# RGBM-06.net
KiCad netlist of a schematic drawn in Altium Designer
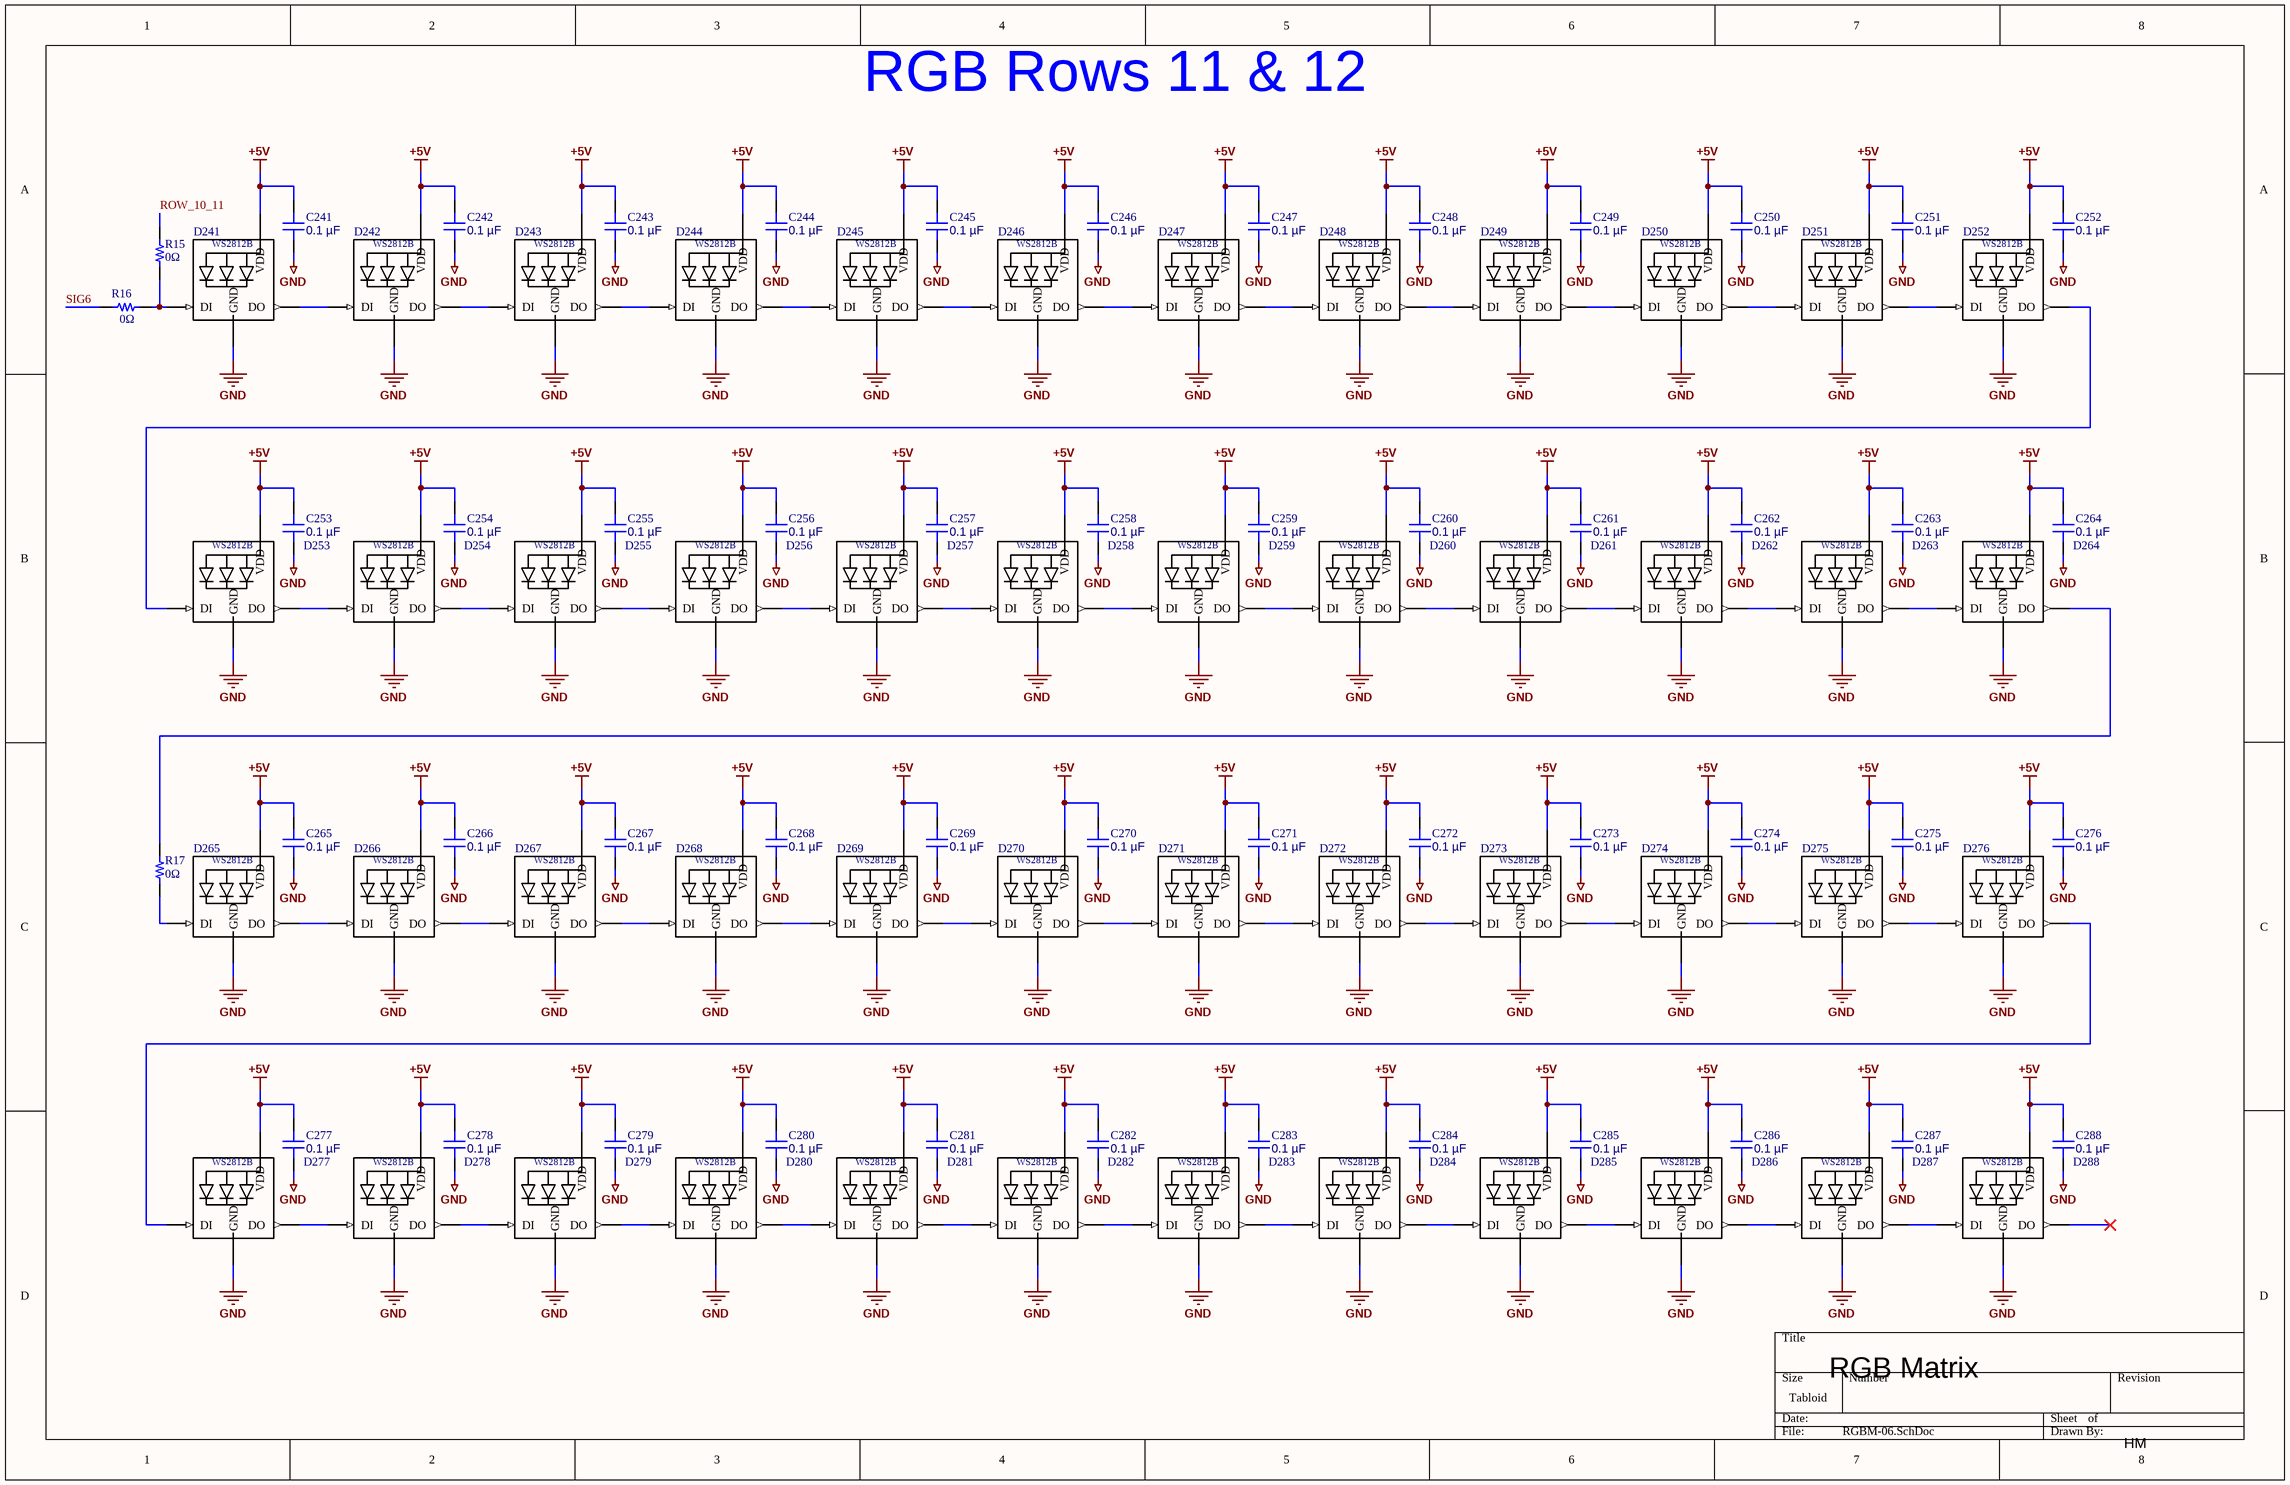
[diagram p0: RGBM-06.SchDoc]

(export (version "E")
  (design (tool "Eeschema 10.0.6"))
  (components
    (comp (ref "C241")
      (value "0.1 µF")
      (footprint "CAP 0603_1608")
      (description "CAP CER 0.1UF 50V X7R 0603")
      (fields
        (field (name "PART NUMBER") "C0603C104K5RAC7411")
        (field (name "CAPACITANCE") "0.1 µF")
        (field (name "MANUFACTURER") "KEMET")
      )
      (libsource (lib "Celestial Altium Library - altium_library") (part "Capacitor"))
    )
    (comp (ref "C242")
      (value "0.1 µF")
      (footprint "CAP 0603_1608")
      (description "CAP CER 0.1UF 50V X7R 0603")
      (fields
        (field (name "PART NUMBER") "C0603C104K5RAC7411")
        (field (name "CAPACITANCE") "0.1 µF")
        (field (name "MANUFACTURER") "KEMET")
      )
      (libsource (lib "Celestial Altium Library - altium_library") (part "Capacitor"))
    )
    (comp (ref "C243")
      (value "0.1 µF")
      (footprint "CAP 0603_1608")
      (description "CAP CER 0.1UF 50V X7R 0603")
      (fields
        (field (name "PART NUMBER") "C0603C104K5RAC7411")
        (field (name "CAPACITANCE") "0.1 µF")
        (field (name "MANUFACTURER") "KEMET")
      )
      (libsource (lib "Celestial Altium Library - altium_library") (part "Capacitor"))
    )
    (comp (ref "C244")
      (value "0.1 µF")
      (footprint "CAP 0603_1608")
      (description "CAP CER 0.1UF 50V X7R 0603")
      (fields
        (field (name "PART NUMBER") "C0603C104K5RAC7411")
        (field (name "CAPACITANCE") "0.1 µF")
        (field (name "MANUFACTURER") "KEMET")
      )
      (libsource (lib "Celestial Altium Library - altium_library") (part "Capacitor"))
    )
    (comp (ref "C245")
      (value "0.1 µF")
      (footprint "CAP 0603_1608")
      (description "CAP CER 0.1UF 50V X7R 0603")
      (fields
        (field (name "PART NUMBER") "C0603C104K5RAC7411")
        (field (name "CAPACITANCE") "0.1 µF")
        (field (name "MANUFACTURER") "KEMET")
      )
      (libsource (lib "Celestial Altium Library - altium_library") (part "Capacitor"))
    )
    (comp (ref "C246")
      (value "0.1 µF")
      (footprint "CAP 0603_1608")
      (description "CAP CER 0.1UF 50V X7R 0603")
      (fields
        (field (name "PART NUMBER") "C0603C104K5RAC7411")
        (field (name "CAPACITANCE") "0.1 µF")
        (field (name "MANUFACTURER") "KEMET")
      )
      (libsource (lib "Celestial Altium Library - altium_library") (part "Capacitor"))
    )
    (comp (ref "C247")
      (value "0.1 µF")
      (footprint "CAP 0603_1608")
      (description "CAP CER 0.1UF 50V X7R 0603")
      (fields
        (field (name "PART NUMBER") "C0603C104K5RAC7411")
        (field (name "CAPACITANCE") "0.1 µF")
        (field (name "MANUFACTURER") "KEMET")
      )
      (libsource (lib "Celestial Altium Library - altium_library") (part "Capacitor"))
    )
    (comp (ref "C248")
      (value "0.1 µF")
      (footprint "CAP 0603_1608")
      (description "CAP CER 0.1UF 50V X7R 0603")
      (fields
        (field (name "PART NUMBER") "C0603C104K5RAC7411")
        (field (name "CAPACITANCE") "0.1 µF")
        (field (name "MANUFACTURER") "KEMET")
      )
      (libsource (lib "Celestial Altium Library - altium_library") (part "Capacitor"))
    )
    (comp (ref "C249")
      (value "0.1 µF")
      (footprint "CAP 0603_1608")
      (description "CAP CER 0.1UF 50V X7R 0603")
      (fields
        (field (name "PART NUMBER") "C0603C104K5RAC7411")
        (field (name "CAPACITANCE") "0.1 µF")
        (field (name "MANUFACTURER") "KEMET")
      )
      (libsource (lib "Celestial Altium Library - altium_library") (part "Capacitor"))
    )
    (comp (ref "C250")
      (value "0.1 µF")
      (footprint "CAP 0603_1608")
      (description "CAP CER 0.1UF 50V X7R 0603")
      (fields
        (field (name "PART NUMBER") "C0603C104K5RAC7411")
        (field (name "CAPACITANCE") "0.1 µF")
        (field (name "MANUFACTURER") "KEMET")
      )
      (libsource (lib "Celestial Altium Library - altium_library") (part "Capacitor"))
    )
    (comp (ref "C251")
      (value "0.1 µF")
      (footprint "CAP 0603_1608")
      (description "CAP CER 0.1UF 50V X7R 0603")
      (fields
        (field (name "PART NUMBER") "C0603C104K5RAC7411")
        (field (name "CAPACITANCE") "0.1 µF")
        (field (name "MANUFACTURER") "KEMET")
      )
      (libsource (lib "Celestial Altium Library - altium_library") (part "Capacitor"))
    )
    (comp (ref "C252")
      (value "0.1 µF")
      (footprint "CAP 0603_1608")
      (description "CAP CER 0.1UF 50V X7R 0603")
      (fields
        (field (name "PART NUMBER") "C0603C104K5RAC7411")
        (field (name "CAPACITANCE") "0.1 µF")
        (field (name "MANUFACTURER") "KEMET")
      )
      (libsource (lib "Celestial Altium Library - altium_library") (part "Capacitor"))
    )
    (comp (ref "C253")
      (value "0.1 µF")
      (footprint "CAP 0603_1608")
      (description "CAP CER 0.1UF 50V X7R 0603")
      (fields
        (field (name "PART NUMBER") "C0603C104K5RAC7411")
        (field (name "CAPACITANCE") "0.1 µF")
        (field (name "MANUFACTURER") "KEMET")
      )
      (libsource (lib "Celestial Altium Library - altium_library") (part "Capacitor"))
    )
    (comp (ref "C254")
      (value "0.1 µF")
      (footprint "CAP 0603_1608")
      (description "CAP CER 0.1UF 50V X7R 0603")
      (fields
        (field (name "PART NUMBER") "C0603C104K5RAC7411")
        (field (name "CAPACITANCE") "0.1 µF")
        (field (name "MANUFACTURER") "KEMET")
      )
      (libsource (lib "Celestial Altium Library - altium_library") (part "Capacitor"))
    )
    (comp (ref "C255")
      (value "0.1 µF")
      (footprint "CAP 0603_1608")
      (description "CAP CER 0.1UF 50V X7R 0603")
      (fields
        (field (name "PART NUMBER") "C0603C104K5RAC7411")
        (field (name "CAPACITANCE") "0.1 µF")
        (field (name "MANUFACTURER") "KEMET")
      )
      (libsource (lib "Celestial Altium Library - altium_library") (part "Capacitor"))
    )
    (comp (ref "C256")
      (value "0.1 µF")
      (footprint "CAP 0603_1608")
      (description "CAP CER 0.1UF 50V X7R 0603")
      (fields
        (field (name "PART NUMBER") "C0603C104K5RAC7411")
        (field (name "CAPACITANCE") "0.1 µF")
        (field (name "MANUFACTURER") "KEMET")
      )
      (libsource (lib "Celestial Altium Library - altium_library") (part "Capacitor"))
    )
    (comp (ref "C257")
      (value "0.1 µF")
      (footprint "CAP 0603_1608")
      (description "CAP CER 0.1UF 50V X7R 0603")
      (fields
        (field (name "PART NUMBER") "C0603C104K5RAC7411")
        (field (name "CAPACITANCE") "0.1 µF")
        (field (name "MANUFACTURER") "KEMET")
      )
      (libsource (lib "Celestial Altium Library - altium_library") (part "Capacitor"))
    )
    (comp (ref "C258")
      (value "0.1 µF")
      (footprint "CAP 0603_1608")
      (description "CAP CER 0.1UF 50V X7R 0603")
      (fields
        (field (name "PART NUMBER") "C0603C104K5RAC7411")
        (field (name "CAPACITANCE") "0.1 µF")
        (field (name "MANUFACTURER") "KEMET")
      )
      (libsource (lib "Celestial Altium Library - altium_library") (part "Capacitor"))
    )
    (comp (ref "C259")
      (value "0.1 µF")
      (footprint "CAP 0603_1608")
      (description "CAP CER 0.1UF 50V X7R 0603")
      (fields
        (field (name "PART NUMBER") "C0603C104K5RAC7411")
        (field (name "CAPACITANCE") "0.1 µF")
        (field (name "MANUFACTURER") "KEMET")
      )
      (libsource (lib "Celestial Altium Library - altium_library") (part "Capacitor"))
    )
    (comp (ref "C260")
      (value "0.1 µF")
      (footprint "CAP 0603_1608")
      (description "CAP CER 0.1UF 50V X7R 0603")
      (fields
        (field (name "PART NUMBER") "C0603C104K5RAC7411")
        (field (name "CAPACITANCE") "0.1 µF")
        (field (name "MANUFACTURER") "KEMET")
      )
      (libsource (lib "Celestial Altium Library - altium_library") (part "Capacitor"))
    )
    (comp (ref "C261")
      (value "0.1 µF")
      (footprint "CAP 0603_1608")
      (description "CAP CER 0.1UF 50V X7R 0603")
      (fields
        (field (name "PART NUMBER") "C0603C104K5RAC7411")
        (field (name "CAPACITANCE") "0.1 µF")
        (field (name "MANUFACTURER") "KEMET")
      )
      (libsource (lib "Celestial Altium Library - altium_library") (part "Capacitor"))
    )
    (comp (ref "C262")
      (value "0.1 µF")
      (footprint "CAP 0603_1608")
      (description "CAP CER 0.1UF 50V X7R 0603")
      (fields
        (field (name "PART NUMBER") "C0603C104K5RAC7411")
        (field (name "CAPACITANCE") "0.1 µF")
        (field (name "MANUFACTURER") "KEMET")
      )
      (libsource (lib "Celestial Altium Library - altium_library") (part "Capacitor"))
    )
    (comp (ref "C263")
      (value "0.1 µF")
      (footprint "CAP 0603_1608")
      (description "CAP CER 0.1UF 50V X7R 0603")
      (fields
        (field (name "PART NUMBER") "C0603C104K5RAC7411")
        (field (name "CAPACITANCE") "0.1 µF")
        (field (name "MANUFACTURER") "KEMET")
      )
      (libsource (lib "Celestial Altium Library - altium_library") (part "Capacitor"))
    )
    (comp (ref "C264")
      (value "0.1 µF")
      (footprint "CAP 0603_1608")
      (description "CAP CER 0.1UF 50V X7R 0603")
      (fields
        (field (name "PART NUMBER") "C0603C104K5RAC7411")
        (field (name "CAPACITANCE") "0.1 µF")
        (field (name "MANUFACTURER") "KEMET")
      )
      (libsource (lib "Celestial Altium Library - altium_library") (part "Capacitor"))
    )
    (comp (ref "C265")
      (value "0.1 µF")
      (footprint "CAP 0603_1608")
      (description "CAP CER 0.1UF 50V X7R 0603")
      (fields
        (field (name "PART NUMBER") "C0603C104K5RAC7411")
        (field (name "CAPACITANCE") "0.1 µF")
        (field (name "MANUFACTURER") "KEMET")
      )
      (libsource (lib "Celestial Altium Library - altium_library") (part "Capacitor"))
    )
    (comp (ref "C266")
      (value "0.1 µF")
      (footprint "CAP 0603_1608")
      (description "CAP CER 0.1UF 50V X7R 0603")
      (fields
        (field (name "PART NUMBER") "C0603C104K5RAC7411")
        (field (name "CAPACITANCE") "0.1 µF")
        (field (name "MANUFACTURER") "KEMET")
      )
      (libsource (lib "Celestial Altium Library - altium_library") (part "Capacitor"))
    )
    (comp (ref "C267")
      (value "0.1 µF")
      (footprint "CAP 0603_1608")
      (description "CAP CER 0.1UF 50V X7R 0603")
      (fields
        (field (name "PART NUMBER") "C0603C104K5RAC7411")
        (field (name "CAPACITANCE") "0.1 µF")
        (field (name "MANUFACTURER") "KEMET")
      )
      (libsource (lib "Celestial Altium Library - altium_library") (part "Capacitor"))
    )
    (comp (ref "C268")
      (value "0.1 µF")
      (footprint "CAP 0603_1608")
      (description "CAP CER 0.1UF 50V X7R 0603")
      (fields
        (field (name "PART NUMBER") "C0603C104K5RAC7411")
        (field (name "CAPACITANCE") "0.1 µF")
        (field (name "MANUFACTURER") "KEMET")
      )
      (libsource (lib "Celestial Altium Library - altium_library") (part "Capacitor"))
    )
    (comp (ref "C269")
      (value "0.1 µF")
      (footprint "CAP 0603_1608")
      (description "CAP CER 0.1UF 50V X7R 0603")
      (fields
        (field (name "PART NUMBER") "C0603C104K5RAC7411")
        (field (name "CAPACITANCE") "0.1 µF")
        (field (name "MANUFACTURER") "KEMET")
      )
      (libsource (lib "Celestial Altium Library - altium_library") (part "Capacitor"))
    )
    (comp (ref "C270")
      (value "0.1 µF")
      (footprint "CAP 0603_1608")
      (description "CAP CER 0.1UF 50V X7R 0603")
      (fields
        (field (name "PART NUMBER") "C0603C104K5RAC7411")
        (field (name "CAPACITANCE") "0.1 µF")
        (field (name "MANUFACTURER") "KEMET")
      )
      (libsource (lib "Celestial Altium Library - altium_library") (part "Capacitor"))
    )
    (comp (ref "C271")
      (value "0.1 µF")
      (footprint "CAP 0603_1608")
      (description "CAP CER 0.1UF 50V X7R 0603")
      (fields
        (field (name "PART NUMBER") "C0603C104K5RAC7411")
        (field (name "CAPACITANCE") "0.1 µF")
        (field (name "MANUFACTURER") "KEMET")
      )
      (libsource (lib "Celestial Altium Library - altium_library") (part "Capacitor"))
    )
    (comp (ref "C272")
      (value "0.1 µF")
      (footprint "CAP 0603_1608")
      (description "CAP CER 0.1UF 50V X7R 0603")
      (fields
        (field (name "PART NUMBER") "C0603C104K5RAC7411")
        (field (name "CAPACITANCE") "0.1 µF")
        (field (name "MANUFACTURER") "KEMET")
      )
      (libsource (lib "Celestial Altium Library - altium_library") (part "Capacitor"))
    )
    (comp (ref "C273")
      (value "0.1 µF")
      (footprint "CAP 0603_1608")
      (description "CAP CER 0.1UF 50V X7R 0603")
      (fields
        (field (name "PART NUMBER") "C0603C104K5RAC7411")
        (field (name "CAPACITANCE") "0.1 µF")
        (field (name "MANUFACTURER") "KEMET")
      )
      (libsource (lib "Celestial Altium Library - altium_library") (part "Capacitor"))
    )
    (comp (ref "C274")
      (value "0.1 µF")
      (footprint "CAP 0603_1608")
      (description "CAP CER 0.1UF 50V X7R 0603")
      (fields
        (field (name "PART NUMBER") "C0603C104K5RAC7411")
        (field (name "CAPACITANCE") "0.1 µF")
        (field (name "MANUFACTURER") "KEMET")
      )
      (libsource (lib "Celestial Altium Library - altium_library") (part "Capacitor"))
    )
    (comp (ref "C275")
      (value "0.1 µF")
      (footprint "CAP 0603_1608")
      (description "CAP CER 0.1UF 50V X7R 0603")
      (fields
        (field (name "PART NUMBER") "C0603C104K5RAC7411")
        (field (name "CAPACITANCE") "0.1 µF")
        (field (name "MANUFACTURER") "KEMET")
      )
      (libsource (lib "Celestial Altium Library - altium_library") (part "Capacitor"))
    )
    (comp (ref "C276")
      (value "0.1 µF")
      (footprint "CAP 0603_1608")
      (description "CAP CER 0.1UF 50V X7R 0603")
      (fields
        (field (name "PART NUMBER") "C0603C104K5RAC7411")
        (field (name "CAPACITANCE") "0.1 µF")
        (field (name "MANUFACTURER") "KEMET")
      )
      (libsource (lib "Celestial Altium Library - altium_library") (part "Capacitor"))
    )
    (comp (ref "C277")
      (value "0.1 µF")
      (footprint "CAP 0603_1608")
      (description "CAP CER 0.1UF 50V X7R 0603")
      (fields
        (field (name "PART NUMBER") "C0603C104K5RAC7411")
        (field (name "CAPACITANCE") "0.1 µF")
        (field (name "MANUFACTURER") "KEMET")
      )
      (libsource (lib "Celestial Altium Library - altium_library") (part "Capacitor"))
    )
    (comp (ref "C278")
      (value "0.1 µF")
      (footprint "CAP 0603_1608")
      (description "CAP CER 0.1UF 50V X7R 0603")
      (fields
        (field (name "PART NUMBER") "C0603C104K5RAC7411")
        (field (name "CAPACITANCE") "0.1 µF")
        (field (name "MANUFACTURER") "KEMET")
      )
      (libsource (lib "Celestial Altium Library - altium_library") (part "Capacitor"))
    )
    (comp (ref "C279")
      (value "0.1 µF")
      (footprint "CAP 0603_1608")
      (description "CAP CER 0.1UF 50V X7R 0603")
      (fields
        (field (name "PART NUMBER") "C0603C104K5RAC7411")
        (field (name "CAPACITANCE") "0.1 µF")
        (field (name "MANUFACTURER") "KEMET")
      )
      (libsource (lib "Celestial Altium Library - altium_library") (part "Capacitor"))
    )
    (comp (ref "C280")
      (value "0.1 µF")
      (footprint "CAP 0603_1608")
      (description "CAP CER 0.1UF 50V X7R 0603")
      (fields
        (field (name "PART NUMBER") "C0603C104K5RAC7411")
        (field (name "CAPACITANCE") "0.1 µF")
        (field (name "MANUFACTURER") "KEMET")
      )
      (libsource (lib "Celestial Altium Library - altium_library") (part "Capacitor"))
    )
    (comp (ref "C281")
      (value "0.1 µF")
      (footprint "CAP 0603_1608")
      (description "CAP CER 0.1UF 50V X7R 0603")
      (fields
        (field (name "PART NUMBER") "C0603C104K5RAC7411")
        (field (name "CAPACITANCE") "0.1 µF")
        (field (name "MANUFACTURER") "KEMET")
      )
      (libsource (lib "Celestial Altium Library - altium_library") (part "Capacitor"))
    )
    (comp (ref "C282")
      (value "0.1 µF")
      (footprint "CAP 0603_1608")
      (description "CAP CER 0.1UF 50V X7R 0603")
      (fields
        (field (name "PART NUMBER") "C0603C104K5RAC7411")
        (field (name "CAPACITANCE") "0.1 µF")
        (field (name "MANUFACTURER") "KEMET")
      )
      (libsource (lib "Celestial Altium Library - altium_library") (part "Capacitor"))
    )
    (comp (ref "C283")
      (value "0.1 µF")
      (footprint "CAP 0603_1608")
      (description "CAP CER 0.1UF 50V X7R 0603")
      (fields
        (field (name "PART NUMBER") "C0603C104K5RAC7411")
        (field (name "CAPACITANCE") "0.1 µF")
        (field (name "MANUFACTURER") "KEMET")
      )
      (libsource (lib "Celestial Altium Library - altium_library") (part "Capacitor"))
    )
    (comp (ref "C284")
      (value "0.1 µF")
      (footprint "CAP 0603_1608")
      (description "CAP CER 0.1UF 50V X7R 0603")
      (fields
        (field (name "PART NUMBER") "C0603C104K5RAC7411")
        (field (name "CAPACITANCE") "0.1 µF")
        (field (name "MANUFACTURER") "KEMET")
      )
      (libsource (lib "Celestial Altium Library - altium_library") (part "Capacitor"))
    )
    (comp (ref "C285")
      (value "0.1 µF")
      (footprint "CAP 0603_1608")
      (description "CAP CER 0.1UF 50V X7R 0603")
      (fields
        (field (name "PART NUMBER") "C0603C104K5RAC7411")
        (field (name "CAPACITANCE") "0.1 µF")
        (field (name "MANUFACTURER") "KEMET")
      )
      (libsource (lib "Celestial Altium Library - altium_library") (part "Capacitor"))
    )
    (comp (ref "C286")
      (value "0.1 µF")
      (footprint "CAP 0603_1608")
      (description "CAP CER 0.1UF 50V X7R 0603")
      (fields
        (field (name "PART NUMBER") "C0603C104K5RAC7411")
        (field (name "CAPACITANCE") "0.1 µF")
        (field (name "MANUFACTURER") "KEMET")
      )
      (libsource (lib "Celestial Altium Library - altium_library") (part "Capacitor"))
    )
    (comp (ref "C287")
      (value "0.1 µF")
      (footprint "CAP 0603_1608")
      (description "CAP CER 0.1UF 50V X7R 0603")
      (fields
        (field (name "PART NUMBER") "C0603C104K5RAC7411")
        (field (name "CAPACITANCE") "0.1 µF")
        (field (name "MANUFACTURER") "KEMET")
      )
      (libsource (lib "Celestial Altium Library - altium_library") (part "Capacitor"))
    )
    (comp (ref "C288")
      (value "0.1 µF")
      (footprint "CAP 0603_1608")
      (description "CAP CER 0.1UF 50V X7R 0603")
      (fields
        (field (name "PART NUMBER") "C0603C104K5RAC7411")
        (field (name "CAPACITANCE") "0.1 µF")
        (field (name "MANUFACTURER") "KEMET")
      )
      (libsource (lib "Celestial Altium Library - altium_library") (part "Capacitor"))
    )
    (comp (ref "D241")
      (value "WS2812B")
      (footprint "*WS2812B_WS2812B(Primary)")
      (description "Intelligent control LED integrated light source")
      (fields (field (name "MF") "Worldsemi"))
      (libsource (lib "WS2812B") (part "WS2812B"))
    )
    (comp (ref "D242")
      (value "WS2812B")
      (footprint "*WS2812B_WS2812B(Primary)")
      (description "Intelligent control LED integrated light source")
      (fields (field (name "MF") "Worldsemi"))
      (libsource (lib "WS2812B") (part "WS2812B"))
    )
    (comp (ref "D243")
      (value "WS2812B")
      (footprint "*WS2812B_WS2812B(Primary)")
      (description "Intelligent control LED integrated light source")
      (fields (field (name "MF") "Worldsemi"))
      (libsource (lib "WS2812B") (part "WS2812B"))
    )
    (comp (ref "D244")
      (value "WS2812B")
      (footprint "*WS2812B_WS2812B(Primary)")
      (description "Intelligent control LED integrated light source")
      (fields (field (name "MF") "Worldsemi"))
      (libsource (lib "WS2812B") (part "WS2812B"))
    )
    (comp (ref "D245")
      (value "WS2812B")
      (footprint "*WS2812B_WS2812B(Primary)")
      (description "Intelligent control LED integrated light source")
      (fields (field (name "MF") "Worldsemi"))
      (libsource (lib "WS2812B") (part "WS2812B"))
    )
    (comp (ref "D246")
      (value "WS2812B")
      (footprint "*WS2812B_WS2812B(Primary)")
      (description "Intelligent control LED integrated light source")
      (fields (field (name "MF") "Worldsemi"))
      (libsource (lib "WS2812B") (part "WS2812B"))
    )
    (comp (ref "D247")
      (value "WS2812B")
      (footprint "*WS2812B_WS2812B(Primary)")
      (description "Intelligent control LED integrated light source")
      (fields (field (name "MF") "Worldsemi"))
      (libsource (lib "WS2812B") (part "WS2812B"))
    )
    (comp (ref "D248")
      (value "WS2812B")
      (footprint "*WS2812B_WS2812B(Primary)")
      (description "Intelligent control LED integrated light source")
      (fields (field (name "MF") "Worldsemi"))
      (libsource (lib "WS2812B") (part "WS2812B"))
    )
    (comp (ref "D249")
      (value "WS2812B")
      (footprint "*WS2812B_WS2812B(Primary)")
      (description "Intelligent control LED integrated light source")
      (fields (field (name "MF") "Worldsemi"))
      (libsource (lib "WS2812B") (part "WS2812B"))
    )
    (comp (ref "D250")
      (value "WS2812B")
      (footprint "*WS2812B_WS2812B(Primary)")
      (description "Intelligent control LED integrated light source")
      (fields (field (name "MF") "Worldsemi"))
      (libsource (lib "WS2812B") (part "WS2812B"))
    )
    (comp (ref "D251")
      (value "WS2812B")
      (footprint "*WS2812B_WS2812B(Primary)")
      (description "Intelligent control LED integrated light source")
      (fields (field (name "MF") "Worldsemi"))
      (libsource (lib "WS2812B") (part "WS2812B"))
    )
    (comp (ref "D252")
      (value "WS2812B")
      (footprint "*WS2812B_WS2812B(Primary)")
      (description "Intelligent control LED integrated light source")
      (fields (field (name "MF") "Worldsemi"))
      (libsource (lib "WS2812B") (part "WS2812B"))
    )
    (comp (ref "D253")
      (value "WS2812B")
      (footprint "*WS2812B_WS2812B(Primary)")
      (description "Intelligent control LED integrated light source")
      (fields (field (name "MF") "Worldsemi"))
      (libsource (lib "WS2812B") (part "WS2812B"))
    )
    (comp (ref "D254")
      (value "WS2812B")
      (footprint "*WS2812B_WS2812B(Primary)")
      (description "Intelligent control LED integrated light source")
      (fields (field (name "MF") "Worldsemi"))
      (libsource (lib "WS2812B") (part "WS2812B"))
    )
    (comp (ref "D255")
      (value "WS2812B")
      (footprint "*WS2812B_WS2812B(Primary)")
      (description "Intelligent control LED integrated light source")
      (fields (field (name "MF") "Worldsemi"))
      (libsource (lib "WS2812B") (part "WS2812B"))
    )
    (comp (ref "D256")
      (value "WS2812B")
      (footprint "*WS2812B_WS2812B(Primary)")
      (description "Intelligent control LED integrated light source")
      (fields (field (name "MF") "Worldsemi"))
      (libsource (lib "WS2812B") (part "WS2812B"))
    )
    (comp (ref "D257")
      (value "WS2812B")
      (footprint "*WS2812B_WS2812B(Primary)")
      (description "Intelligent control LED integrated light source")
      (fields (field (name "MF") "Worldsemi"))
      (libsource (lib "WS2812B") (part "WS2812B"))
    )
    (comp (ref "D258")
      (value "WS2812B")
      (footprint "*WS2812B_WS2812B(Primary)")
      (description "Intelligent control LED integrated light source")
      (fields (field (name "MF") "Worldsemi"))
      (libsource (lib "WS2812B") (part "WS2812B"))
    )
    (comp (ref "D259")
      (value "WS2812B")
      (footprint "*WS2812B_WS2812B(Primary)")
      (description "Intelligent control LED integrated light source")
      (fields (field (name "MF") "Worldsemi"))
      (libsource (lib "WS2812B") (part "WS2812B"))
    )
    (comp (ref "D260")
      (value "WS2812B")
      (footprint "*WS2812B_WS2812B(Primary)")
      (description "Intelligent control LED integrated light source")
      (fields (field (name "MF") "Worldsemi"))
      (libsource (lib "WS2812B") (part "WS2812B"))
    )
    (comp (ref "D261")
      (value "WS2812B")
      (footprint "*WS2812B_WS2812B(Primary)")
      (description "Intelligent control LED integrated light source")
      (fields (field (name "MF") "Worldsemi"))
      (libsource (lib "WS2812B") (part "WS2812B"))
    )
    (comp (ref "D262")
      (value "WS2812B")
      (footprint "*WS2812B_WS2812B(Primary)")
      (description "Intelligent control LED integrated light source")
      (fields (field (name "MF") "Worldsemi"))
      (libsource (lib "WS2812B") (part "WS2812B"))
    )
    (comp (ref "D263")
      (value "WS2812B")
      (footprint "*WS2812B_WS2812B(Primary)")
      (description "Intelligent control LED integrated light source")
      (fields (field (name "MF") "Worldsemi"))
      (libsource (lib "WS2812B") (part "WS2812B"))
    )
    (comp (ref "D264")
      (value "WS2812B")
      (footprint "*WS2812B_WS2812B(Primary)")
      (description "Intelligent control LED integrated light source")
      (fields (field (name "MF") "Worldsemi"))
      (libsource (lib "WS2812B") (part "WS2812B"))
    )
    (comp (ref "D265")
      (value "WS2812B")
      (footprint "*WS2812B_WS2812B(Primary)")
      (description "Intelligent control LED integrated light source")
      (fields (field (name "MF") "Worldsemi"))
      (libsource (lib "WS2812B") (part "WS2812B"))
    )
    (comp (ref "D266")
      (value "WS2812B")
      (footprint "*WS2812B_WS2812B(Primary)")
      (description "Intelligent control LED integrated light source")
      (fields (field (name "MF") "Worldsemi"))
      (libsource (lib "WS2812B") (part "WS2812B"))
    )
    (comp (ref "D267")
      (value "WS2812B")
      (footprint "*WS2812B_WS2812B(Primary)")
      (description "Intelligent control LED integrated light source")
      (fields (field (name "MF") "Worldsemi"))
      (libsource (lib "WS2812B") (part "WS2812B"))
    )
    (comp (ref "D268")
      (value "WS2812B")
      (footprint "*WS2812B_WS2812B(Primary)")
      (description "Intelligent control LED integrated light source")
      (fields (field (name "MF") "Worldsemi"))
      (libsource (lib "WS2812B") (part "WS2812B"))
    )
    (comp (ref "D269")
      (value "WS2812B")
      (footprint "*WS2812B_WS2812B(Primary)")
      (description "Intelligent control LED integrated light source")
      (fields (field (name "MF") "Worldsemi"))
      (libsource (lib "WS2812B") (part "WS2812B"))
    )
    (comp (ref "D270")
      (value "WS2812B")
      (footprint "*WS2812B_WS2812B(Primary)")
      (description "Intelligent control LED integrated light source")
      (fields (field (name "MF") "Worldsemi"))
      (libsource (lib "WS2812B") (part "WS2812B"))
    )
    (comp (ref "D271")
      (value "WS2812B")
      (footprint "*WS2812B_WS2812B(Primary)")
      (description "Intelligent control LED integrated light source")
      (fields (field (name "MF") "Worldsemi"))
      (libsource (lib "WS2812B") (part "WS2812B"))
    )
    (comp (ref "D272")
      (value "WS2812B")
      (footprint "*WS2812B_WS2812B(Primary)")
      (description "Intelligent control LED integrated light source")
      (fields (field (name "MF") "Worldsemi"))
      (libsource (lib "WS2812B") (part "WS2812B"))
    )
    (comp (ref "D273")
      (value "WS2812B")
      (footprint "*WS2812B_WS2812B(Primary)")
      (description "Intelligent control LED integrated light source")
      (fields (field (name "MF") "Worldsemi"))
      (libsource (lib "WS2812B") (part "WS2812B"))
    )
    (comp (ref "D274")
      (value "WS2812B")
      (footprint "*WS2812B_WS2812B(Primary)")
      (description "Intelligent control LED integrated light source")
      (fields (field (name "MF") "Worldsemi"))
      (libsource (lib "WS2812B") (part "WS2812B"))
    )
    (comp (ref "D275")
      (value "WS2812B")
      (footprint "*WS2812B_WS2812B(Primary)")
      (description "Intelligent control LED integrated light source")
      (fields (field (name "MF") "Worldsemi"))
      (libsource (lib "WS2812B") (part "WS2812B"))
    )
    (comp (ref "D276")
      (value "WS2812B")
      (footprint "*WS2812B_WS2812B(Primary)")
      (description "Intelligent control LED integrated light source")
      (fields (field (name "MF") "Worldsemi"))
      (libsource (lib "WS2812B") (part "WS2812B"))
    )
    (comp (ref "D277")
      (value "WS2812B")
      (footprint "*WS2812B_WS2812B(Primary)")
      (description "Intelligent control LED integrated light source")
      (fields (field (name "MF") "Worldsemi"))
      (libsource (lib "WS2812B") (part "WS2812B"))
    )
    (comp (ref "D278")
      (value "WS2812B")
      (footprint "*WS2812B_WS2812B(Primary)")
      (description "Intelligent control LED integrated light source")
      (fields (field (name "MF") "Worldsemi"))
      (libsource (lib "WS2812B") (part "WS2812B"))
    )
    (comp (ref "D279")
      (value "WS2812B")
      (footprint "*WS2812B_WS2812B(Primary)")
      (description "Intelligent control LED integrated light source")
      (fields (field (name "MF") "Worldsemi"))
      (libsource (lib "WS2812B") (part "WS2812B"))
    )
    (comp (ref "D280")
      (value "WS2812B")
      (footprint "*WS2812B_WS2812B(Primary)")
      (description "Intelligent control LED integrated light source")
      (fields (field (name "MF") "Worldsemi"))
      (libsource (lib "WS2812B") (part "WS2812B"))
    )
    (comp (ref "D281")
      (value "WS2812B")
      (footprint "*WS2812B_WS2812B(Primary)")
      (description "Intelligent control LED integrated light source")
      (fields (field (name "MF") "Worldsemi"))
      (libsource (lib "WS2812B") (part "WS2812B"))
    )
    (comp (ref "D282")
      (value "WS2812B")
      (footprint "*WS2812B_WS2812B(Primary)")
      (description "Intelligent control LED integrated light source")
      (fields (field (name "MF") "Worldsemi"))
      (libsource (lib "WS2812B") (part "WS2812B"))
    )
    (comp (ref "D283")
      (value "WS2812B")
      (footprint "*WS2812B_WS2812B(Primary)")
      (description "Intelligent control LED integrated light source")
      (fields (field (name "MF") "Worldsemi"))
      (libsource (lib "WS2812B") (part "WS2812B"))
    )
    (comp (ref "D284")
      (value "WS2812B")
      (footprint "*WS2812B_WS2812B(Primary)")
      (description "Intelligent control LED integrated light source")
      (fields (field (name "MF") "Worldsemi"))
      (libsource (lib "WS2812B") (part "WS2812B"))
    )
    (comp (ref "D285")
      (value "WS2812B")
      (footprint "*WS2812B_WS2812B(Primary)")
      (description "Intelligent control LED integrated light source")
      (fields (field (name "MF") "Worldsemi"))
      (libsource (lib "WS2812B") (part "WS2812B"))
    )
    (comp (ref "D286")
      (value "WS2812B")
      (footprint "*WS2812B_WS2812B(Primary)")
      (description "Intelligent control LED integrated light source")
      (fields (field (name "MF") "Worldsemi"))
      (libsource (lib "WS2812B") (part "WS2812B"))
    )
    (comp (ref "D287")
      (value "WS2812B")
      (footprint "*WS2812B_WS2812B(Primary)")
      (description "Intelligent control LED integrated light source")
      (fields (field (name "MF") "Worldsemi"))
      (libsource (lib "WS2812B") (part "WS2812B"))
    )
    (comp (ref "D288")
      (value "WS2812B")
      (footprint "*WS2812B_WS2812B(Primary)")
      (description "Intelligent control LED integrated light source")
      (fields (field (name "MF") "Worldsemi"))
      (libsource (lib "WS2812B") (part "WS2812B"))
    )
    (comp (ref "R15")
      (value "0Ω")
      (footprint "RES 0603_1608")
      (description "RES SMD 0 OHM JUMPER 0603")
      (fields (field (name "PART NUMBER") "YJP1608-R001") (field (name "MANUFACTURER") "Susumu"))
      (libsource (lib "Celestial Altium Library - altium_library") (part "Resistor"))
    )
    (comp (ref "R16")
      (value "0Ω")
      (footprint "RES 0603_1608")
      (description "RES SMD 0 OHM JUMPER 0603")
      (fields (field (name "PART NUMBER") "YJP1608-R001") (field (name "MANUFACTURER") "Susumu"))
      (libsource (lib "Celestial Altium Library - altium_library") (part "Resistor"))
    )
    (comp (ref "R17")
      (value "0Ω")
      (footprint "RES 0603_1608")
      (description "RES SMD 0 OHM JUMPER 0603")
      (fields (field (name "PART NUMBER") "YJP1608-R001") (field (name "MANUFACTURER") "Susumu"))
      (libsource (lib "Celestial Altium Library - altium_library") (part "Resistor"))
    )
  )
  (nets
    (net (code "1") (name "+5V") (class "Default")
      (node (ref "C241") (pin "2") (pinfunction "2_2") (pintype "passive"))
      (node (ref "C242") (pin "2") (pinfunction "2_2") (pintype "passive"))
      (node (ref "C243") (pin "2") (pinfunction "2_2") (pintype "passive"))
      (node (ref "C244") (pin "2") (pinfunction "2_2") (pintype "passive"))
      (node (ref "C245") (pin "2") (pinfunction "2_2") (pintype "passive"))
      (node (ref "C246") (pin "2") (pinfunction "2_2") (pintype "passive"))
      (node (ref "C247") (pin "2") (pinfunction "2_2") (pintype "passive"))
      (node (ref "C248") (pin "2") (pinfunction "2_2") (pintype "passive"))
      (node (ref "C249") (pin "2") (pinfunction "2_2") (pintype "passive"))
      (node (ref "C250") (pin "2") (pinfunction "2_2") (pintype "passive"))
      (node (ref "C251") (pin "2") (pinfunction "2_2") (pintype "passive"))
      (node (ref "C252") (pin "2") (pinfunction "2_2") (pintype "passive"))
      (node (ref "C253") (pin "2") (pinfunction "2_2") (pintype "passive"))
      (node (ref "C254") (pin "2") (pinfunction "2_2") (pintype "passive"))
      (node (ref "C255") (pin "2") (pinfunction "2_2") (pintype "passive"))
      (node (ref "C256") (pin "2") (pinfunction "2_2") (pintype "passive"))
      (node (ref "C257") (pin "2") (pinfunction "2_2") (pintype "passive"))
      (node (ref "C258") (pin "2") (pinfunction "2_2") (pintype "passive"))
      (node (ref "C259") (pin "2") (pinfunction "2_2") (pintype "passive"))
      (node (ref "C260") (pin "2") (pinfunction "2_2") (pintype "passive"))
      (node (ref "C261") (pin "2") (pinfunction "2_2") (pintype "passive"))
      (node (ref "C262") (pin "2") (pinfunction "2_2") (pintype "passive"))
      (node (ref "C263") (pin "2") (pinfunction "2_2") (pintype "passive"))
      (node (ref "C264") (pin "2") (pinfunction "2_2") (pintype "passive"))
      (node (ref "C265") (pin "2") (pinfunction "2_2") (pintype "passive"))
      (node (ref "C266") (pin "2") (pinfunction "2_2") (pintype "passive"))
      (node (ref "C267") (pin "2") (pinfunction "2_2") (pintype "passive"))
      (node (ref "C268") (pin "2") (pinfunction "2_2") (pintype "passive"))
      (node (ref "C269") (pin "2") (pinfunction "2_2") (pintype "passive"))
      (node (ref "C270") (pin "2") (pinfunction "2_2") (pintype "passive"))
      (node (ref "C271") (pin "2") (pinfunction "2_2") (pintype "passive"))
      (node (ref "C272") (pin "2") (pinfunction "2_2") (pintype "passive"))
      (node (ref "C273") (pin "2") (pinfunction "2_2") (pintype "passive"))
      (node (ref "C274") (pin "2") (pinfunction "2_2") (pintype "passive"))
      (node (ref "C275") (pin "2") (pinfunction "2_2") (pintype "passive"))
      (node (ref "C276") (pin "2") (pinfunction "2_2") (pintype "passive"))
      (node (ref "C277") (pin "2") (pinfunction "2_2") (pintype "passive"))
      (node (ref "C278") (pin "2") (pinfunction "2_2") (pintype "passive"))
      (node (ref "C279") (pin "2") (pinfunction "2_2") (pintype "passive"))
      (node (ref "C280") (pin "2") (pinfunction "2_2") (pintype "passive"))
      (node (ref "C281") (pin "2") (pinfunction "2_2") (pintype "passive"))
      (node (ref "C282") (pin "2") (pinfunction "2_2") (pintype "passive"))
      (node (ref "C283") (pin "2") (pinfunction "2_2") (pintype "passive"))
      (node (ref "C284") (pin "2") (pinfunction "2_2") (pintype "passive"))
      (node (ref "C285") (pin "2") (pinfunction "2_2") (pintype "passive"))
      (node (ref "C286") (pin "2") (pinfunction "2_2") (pintype "passive"))
      (node (ref "C287") (pin "2") (pinfunction "2_2") (pintype "passive"))
      (node (ref "C288") (pin "2") (pinfunction "2_2") (pintype "passive"))
      (node (ref "D241") (pin "1-VDD") (pinfunction "VDD_1-VDD") (pintype "power_in"))
      (node (ref "D242") (pin "1-VDD") (pinfunction "VDD_1-VDD") (pintype "power_in"))
      (node (ref "D243") (pin "1-VDD") (pinfunction "VDD_1-VDD") (pintype "power_in"))
      (node (ref "D244") (pin "1-VDD") (pinfunction "VDD_1-VDD") (pintype "power_in"))
      (node (ref "D245") (pin "1-VDD") (pinfunction "VDD_1-VDD") (pintype "power_in"))
      (node (ref "D246") (pin "1-VDD") (pinfunction "VDD_1-VDD") (pintype "power_in"))
      (node (ref "D247") (pin "1-VDD") (pinfunction "VDD_1-VDD") (pintype "power_in"))
      (node (ref "D248") (pin "1-VDD") (pinfunction "VDD_1-VDD") (pintype "power_in"))
      (node (ref "D249") (pin "1-VDD") (pinfunction "VDD_1-VDD") (pintype "power_in"))
      (node (ref "D250") (pin "1-VDD") (pinfunction "VDD_1-VDD") (pintype "power_in"))
      (node (ref "D251") (pin "1-VDD") (pinfunction "VDD_1-VDD") (pintype "power_in"))
      (node (ref "D252") (pin "1-VDD") (pinfunction "VDD_1-VDD") (pintype "power_in"))
      (node (ref "D253") (pin "1-VDD") (pinfunction "VDD_1-VDD") (pintype "power_in"))
      (node (ref "D254") (pin "1-VDD") (pinfunction "VDD_1-VDD") (pintype "power_in"))
      (node (ref "D255") (pin "1-VDD") (pinfunction "VDD_1-VDD") (pintype "power_in"))
      (node (ref "D256") (pin "1-VDD") (pinfunction "VDD_1-VDD") (pintype "power_in"))
      (node (ref "D257") (pin "1-VDD") (pinfunction "VDD_1-VDD") (pintype "power_in"))
      (node (ref "D258") (pin "1-VDD") (pinfunction "VDD_1-VDD") (pintype "power_in"))
      (node (ref "D259") (pin "1-VDD") (pinfunction "VDD_1-VDD") (pintype "power_in"))
      (node (ref "D260") (pin "1-VDD") (pinfunction "VDD_1-VDD") (pintype "power_in"))
      (node (ref "D261") (pin "1-VDD") (pinfunction "VDD_1-VDD") (pintype "power_in"))
      (node (ref "D262") (pin "1-VDD") (pinfunction "VDD_1-VDD") (pintype "power_in"))
      (node (ref "D263") (pin "1-VDD") (pinfunction "VDD_1-VDD") (pintype "power_in"))
      (node (ref "D264") (pin "1-VDD") (pinfunction "VDD_1-VDD") (pintype "power_in"))
      (node (ref "D265") (pin "1-VDD") (pinfunction "VDD_1-VDD") (pintype "power_in"))
      (node (ref "D266") (pin "1-VDD") (pinfunction "VDD_1-VDD") (pintype "power_in"))
      (node (ref "D267") (pin "1-VDD") (pinfunction "VDD_1-VDD") (pintype "power_in"))
      (node (ref "D268") (pin "1-VDD") (pinfunction "VDD_1-VDD") (pintype "power_in"))
      (node (ref "D269") (pin "1-VDD") (pinfunction "VDD_1-VDD") (pintype "power_in"))
      (node (ref "D270") (pin "1-VDD") (pinfunction "VDD_1-VDD") (pintype "power_in"))
      (node (ref "D271") (pin "1-VDD") (pinfunction "VDD_1-VDD") (pintype "power_in"))
      (node (ref "D272") (pin "1-VDD") (pinfunction "VDD_1-VDD") (pintype "power_in"))
      (node (ref "D273") (pin "1-VDD") (pinfunction "VDD_1-VDD") (pintype "power_in"))
      (node (ref "D274") (pin "1-VDD") (pinfunction "VDD_1-VDD") (pintype "power_in"))
      (node (ref "D275") (pin "1-VDD") (pinfunction "VDD_1-VDD") (pintype "power_in"))
      (node (ref "D276") (pin "1-VDD") (pinfunction "VDD_1-VDD") (pintype "power_in"))
      (node (ref "D277") (pin "1-VDD") (pinfunction "VDD_1-VDD") (pintype "power_in"))
      (node (ref "D278") (pin "1-VDD") (pinfunction "VDD_1-VDD") (pintype "power_in"))
      (node (ref "D279") (pin "1-VDD") (pinfunction "VDD_1-VDD") (pintype "power_in"))
      (node (ref "D280") (pin "1-VDD") (pinfunction "VDD_1-VDD") (pintype "power_in"))
      (node (ref "D281") (pin "1-VDD") (pinfunction "VDD_1-VDD") (pintype "power_in"))
      (node (ref "D282") (pin "1-VDD") (pinfunction "VDD_1-VDD") (pintype "power_in"))
      (node (ref "D283") (pin "1-VDD") (pinfunction "VDD_1-VDD") (pintype "power_in"))
      (node (ref "D284") (pin "1-VDD") (pinfunction "VDD_1-VDD") (pintype "power_in"))
      (node (ref "D285") (pin "1-VDD") (pinfunction "VDD_1-VDD") (pintype "power_in"))
      (node (ref "D286") (pin "1-VDD") (pinfunction "VDD_1-VDD") (pintype "power_in"))
      (node (ref "D287") (pin "1-VDD") (pinfunction "VDD_1-VDD") (pintype "power_in"))
      (node (ref "D288") (pin "1-VDD") (pinfunction "VDD_1-VDD") (pintype "power_in"))
    )
    (net (code "2") (name "/ROW_10_11") (class "Default")
      (node (ref "R15") (pin "2") (pinfunction "2_2") (pintype "passive"))
    )
    (net (code "3") (name "/SIG6") (class "Default")
      (node (ref "R16") (pin "1") (pinfunction "1_1") (pintype "passive"))
    )
    (net (code "4") (name "GND") (class "Default")
      (node (ref "C241") (pin "1") (pinfunction "1_1") (pintype "passive"))
      (node (ref "C242") (pin "1") (pinfunction "1_1") (pintype "passive"))
      (node (ref "C243") (pin "1") (pinfunction "1_1") (pintype "passive"))
      (node (ref "C244") (pin "1") (pinfunction "1_1") (pintype "passive"))
      (node (ref "C245") (pin "1") (pinfunction "1_1") (pintype "passive"))
      (node (ref "C246") (pin "1") (pinfunction "1_1") (pintype "passive"))
      (node (ref "C247") (pin "1") (pinfunction "1_1") (pintype "passive"))
      (node (ref "C248") (pin "1") (pinfunction "1_1") (pintype "passive"))
      (node (ref "C249") (pin "1") (pinfunction "1_1") (pintype "passive"))
      (node (ref "C250") (pin "1") (pinfunction "1_1") (pintype "passive"))
      (node (ref "C251") (pin "1") (pinfunction "1_1") (pintype "passive"))
      (node (ref "C252") (pin "1") (pinfunction "1_1") (pintype "passive"))
      (node (ref "C253") (pin "1") (pinfunction "1_1") (pintype "passive"))
      (node (ref "C254") (pin "1") (pinfunction "1_1") (pintype "passive"))
      (node (ref "C255") (pin "1") (pinfunction "1_1") (pintype "passive"))
      (node (ref "C256") (pin "1") (pinfunction "1_1") (pintype "passive"))
      (node (ref "C257") (pin "1") (pinfunction "1_1") (pintype "passive"))
      (node (ref "C258") (pin "1") (pinfunction "1_1") (pintype "passive"))
      (node (ref "C259") (pin "1") (pinfunction "1_1") (pintype "passive"))
      (node (ref "C260") (pin "1") (pinfunction "1_1") (pintype "passive"))
      (node (ref "C261") (pin "1") (pinfunction "1_1") (pintype "passive"))
      (node (ref "C262") (pin "1") (pinfunction "1_1") (pintype "passive"))
      (node (ref "C263") (pin "1") (pinfunction "1_1") (pintype "passive"))
      (node (ref "C264") (pin "1") (pinfunction "1_1") (pintype "passive"))
      (node (ref "C265") (pin "1") (pinfunction "1_1") (pintype "passive"))
      (node (ref "C266") (pin "1") (pinfunction "1_1") (pintype "passive"))
      (node (ref "C267") (pin "1") (pinfunction "1_1") (pintype "passive"))
      (node (ref "C268") (pin "1") (pinfunction "1_1") (pintype "passive"))
      (node (ref "C269") (pin "1") (pinfunction "1_1") (pintype "passive"))
      (node (ref "C270") (pin "1") (pinfunction "1_1") (pintype "passive"))
      (node (ref "C271") (pin "1") (pinfunction "1_1") (pintype "passive"))
      (node (ref "C272") (pin "1") (pinfunction "1_1") (pintype "passive"))
      (node (ref "C273") (pin "1") (pinfunction "1_1") (pintype "passive"))
      (node (ref "C274") (pin "1") (pinfunction "1_1") (pintype "passive"))
      (node (ref "C275") (pin "1") (pinfunction "1_1") (pintype "passive"))
      (node (ref "C276") (pin "1") (pinfunction "1_1") (pintype "passive"))
      (node (ref "C277") (pin "1") (pinfunction "1_1") (pintype "passive"))
      (node (ref "C278") (pin "1") (pinfunction "1_1") (pintype "passive"))
      (node (ref "C279") (pin "1") (pinfunction "1_1") (pintype "passive"))
      (node (ref "C280") (pin "1") (pinfunction "1_1") (pintype "passive"))
      (node (ref "C281") (pin "1") (pinfunction "1_1") (pintype "passive"))
      (node (ref "C282") (pin "1") (pinfunction "1_1") (pintype "passive"))
      (node (ref "C283") (pin "1") (pinfunction "1_1") (pintype "passive"))
      (node (ref "C284") (pin "1") (pinfunction "1_1") (pintype "passive"))
      (node (ref "C285") (pin "1") (pinfunction "1_1") (pintype "passive"))
      (node (ref "C286") (pin "1") (pinfunction "1_1") (pintype "passive"))
      (node (ref "C287") (pin "1") (pinfunction "1_1") (pintype "passive"))
      (node (ref "C288") (pin "1") (pinfunction "1_1") (pintype "passive"))
      (node (ref "D241") (pin "3-GND") (pinfunction "GND_3-GND") (pintype "power_in"))
      (node (ref "D242") (pin "3-GND") (pinfunction "GND_3-GND") (pintype "power_in"))
      (node (ref "D243") (pin "3-GND") (pinfunction "GND_3-GND") (pintype "power_in"))
      (node (ref "D244") (pin "3-GND") (pinfunction "GND_3-GND") (pintype "power_in"))
      (node (ref "D245") (pin "3-GND") (pinfunction "GND_3-GND") (pintype "power_in"))
      (node (ref "D246") (pin "3-GND") (pinfunction "GND_3-GND") (pintype "power_in"))
      (node (ref "D247") (pin "3-GND") (pinfunction "GND_3-GND") (pintype "power_in"))
      (node (ref "D248") (pin "3-GND") (pinfunction "GND_3-GND") (pintype "power_in"))
      (node (ref "D249") (pin "3-GND") (pinfunction "GND_3-GND") (pintype "power_in"))
      (node (ref "D250") (pin "3-GND") (pinfunction "GND_3-GND") (pintype "power_in"))
      (node (ref "D251") (pin "3-GND") (pinfunction "GND_3-GND") (pintype "power_in"))
      (node (ref "D252") (pin "3-GND") (pinfunction "GND_3-GND") (pintype "power_in"))
      (node (ref "D253") (pin "3-GND") (pinfunction "GND_3-GND") (pintype "power_in"))
      (node (ref "D254") (pin "3-GND") (pinfunction "GND_3-GND") (pintype "power_in"))
      (node (ref "D255") (pin "3-GND") (pinfunction "GND_3-GND") (pintype "power_in"))
      (node (ref "D256") (pin "3-GND") (pinfunction "GND_3-GND") (pintype "power_in"))
      (node (ref "D257") (pin "3-GND") (pinfunction "GND_3-GND") (pintype "power_in"))
      (node (ref "D258") (pin "3-GND") (pinfunction "GND_3-GND") (pintype "power_in"))
      (node (ref "D259") (pin "3-GND") (pinfunction "GND_3-GND") (pintype "power_in"))
      (node (ref "D260") (pin "3-GND") (pinfunction "GND_3-GND") (pintype "power_in"))
      (node (ref "D261") (pin "3-GND") (pinfunction "GND_3-GND") (pintype "power_in"))
      (node (ref "D262") (pin "3-GND") (pinfunction "GND_3-GND") (pintype "power_in"))
      (node (ref "D263") (pin "3-GND") (pinfunction "GND_3-GND") (pintype "power_in"))
      (node (ref "D264") (pin "3-GND") (pinfunction "GND_3-GND") (pintype "power_in"))
      (node (ref "D265") (pin "3-GND") (pinfunction "GND_3-GND") (pintype "power_in"))
      (node (ref "D266") (pin "3-GND") (pinfunction "GND_3-GND") (pintype "power_in"))
      (node (ref "D267") (pin "3-GND") (pinfunction "GND_3-GND") (pintype "power_in"))
      (node (ref "D268") (pin "3-GND") (pinfunction "GND_3-GND") (pintype "power_in"))
      (node (ref "D269") (pin "3-GND") (pinfunction "GND_3-GND") (pintype "power_in"))
      (node (ref "D270") (pin "3-GND") (pinfunction "GND_3-GND") (pintype "power_in"))
      (node (ref "D271") (pin "3-GND") (pinfunction "GND_3-GND") (pintype "power_in"))
      (node (ref "D272") (pin "3-GND") (pinfunction "GND_3-GND") (pintype "power_in"))
      (node (ref "D273") (pin "3-GND") (pinfunction "GND_3-GND") (pintype "power_in"))
      (node (ref "D274") (pin "3-GND") (pinfunction "GND_3-GND") (pintype "power_in"))
      (node (ref "D275") (pin "3-GND") (pinfunction "GND_3-GND") (pintype "power_in"))
      (node (ref "D276") (pin "3-GND") (pinfunction "GND_3-GND") (pintype "power_in"))
      (node (ref "D277") (pin "3-GND") (pinfunction "GND_3-GND") (pintype "power_in"))
      (node (ref "D278") (pin "3-GND") (pinfunction "GND_3-GND") (pintype "power_in"))
      (node (ref "D279") (pin "3-GND") (pinfunction "GND_3-GND") (pintype "power_in"))
      (node (ref "D280") (pin "3-GND") (pinfunction "GND_3-GND") (pintype "power_in"))
      (node (ref "D281") (pin "3-GND") (pinfunction "GND_3-GND") (pintype "power_in"))
      (node (ref "D282") (pin "3-GND") (pinfunction "GND_3-GND") (pintype "power_in"))
      (node (ref "D283") (pin "3-GND") (pinfunction "GND_3-GND") (pintype "power_in"))
      (node (ref "D284") (pin "3-GND") (pinfunction "GND_3-GND") (pintype "power_in"))
      (node (ref "D285") (pin "3-GND") (pinfunction "GND_3-GND") (pintype "power_in"))
      (node (ref "D286") (pin "3-GND") (pinfunction "GND_3-GND") (pintype "power_in"))
      (node (ref "D287") (pin "3-GND") (pinfunction "GND_3-GND") (pintype "power_in"))
      (node (ref "D288") (pin "3-GND") (pinfunction "GND_3-GND") (pintype "power_in"))
    )
    (net (code "5") (name "Net-(D241-DI)") (class "Default")
      (node (ref "D241") (pin "4-DIN") (pinfunction "DI_4-DIN") (pintype "input"))
      (node (ref "R15") (pin "1") (pinfunction "1_1") (pintype "passive"))
      (node (ref "R16") (pin "2") (pinfunction "2_2") (pintype "passive"))
    )
    (net (code "6") (name "Net-(D241-DO)") (class "Default")
      (node (ref "D241") (pin "2-DOUT") (pinfunction "DO_2-DOUT") (pintype "output"))
      (node (ref "D242") (pin "4-DIN") (pinfunction "DI_4-DIN") (pintype "input"))
    )
    (net (code "7") (name "Net-(D242-DO)") (class "Default")
      (node (ref "D242") (pin "2-DOUT") (pinfunction "DO_2-DOUT") (pintype "output"))
      (node (ref "D243") (pin "4-DIN") (pinfunction "DI_4-DIN") (pintype "input"))
    )
    (net (code "8") (name "Net-(D243-DO)") (class "Default")
      (node (ref "D243") (pin "2-DOUT") (pinfunction "DO_2-DOUT") (pintype "output"))
      (node (ref "D244") (pin "4-DIN") (pinfunction "DI_4-DIN") (pintype "input"))
    )
    (net (code "9") (name "Net-(D244-DO)") (class "Default")
      (node (ref "D244") (pin "2-DOUT") (pinfunction "DO_2-DOUT") (pintype "output"))
      (node (ref "D245") (pin "4-DIN") (pinfunction "DI_4-DIN") (pintype "input"))
    )
    (net (code "10") (name "Net-(D245-DO)") (class "Default")
      (node (ref "D245") (pin "2-DOUT") (pinfunction "DO_2-DOUT") (pintype "output"))
      (node (ref "D246") (pin "4-DIN") (pinfunction "DI_4-DIN") (pintype "input"))
    )
    (net (code "11") (name "Net-(D246-DO)") (class "Default")
      (node (ref "D246") (pin "2-DOUT") (pinfunction "DO_2-DOUT") (pintype "output"))
      (node (ref "D247") (pin "4-DIN") (pinfunction "DI_4-DIN") (pintype "input"))
    )
    (net (code "12") (name "Net-(D247-DO)") (class "Default")
      (node (ref "D247") (pin "2-DOUT") (pinfunction "DO_2-DOUT") (pintype "output"))
      (node (ref "D248") (pin "4-DIN") (pinfunction "DI_4-DIN") (pintype "input"))
    )
    (net (code "13") (name "Net-(D248-DO)") (class "Default")
      (node (ref "D248") (pin "2-DOUT") (pinfunction "DO_2-DOUT") (pintype "output"))
      (node (ref "D249") (pin "4-DIN") (pinfunction "DI_4-DIN") (pintype "input"))
    )
    (net (code "14") (name "Net-(D249-DO)") (class "Default")
      (node (ref "D249") (pin "2-DOUT") (pinfunction "DO_2-DOUT") (pintype "output"))
      (node (ref "D250") (pin "4-DIN") (pinfunction "DI_4-DIN") (pintype "input"))
    )
    (net (code "15") (name "Net-(D250-DO)") (class "Default")
      (node (ref "D250") (pin "2-DOUT") (pinfunction "DO_2-DOUT") (pintype "output"))
      (node (ref "D251") (pin "4-DIN") (pinfunction "DI_4-DIN") (pintype "input"))
    )
    (net (code "16") (name "Net-(D251-DO)") (class "Default")
      (node (ref "D251") (pin "2-DOUT") (pinfunction "DO_2-DOUT") (pintype "output"))
      (node (ref "D252") (pin "4-DIN") (pinfunction "DI_4-DIN") (pintype "input"))
    )
    (net (code "17") (name "Net-(D252-DO)") (class "Default")
      (node (ref "D252") (pin "2-DOUT") (pinfunction "DO_2-DOUT") (pintype "output"))
      (node (ref "D253") (pin "4-DIN") (pinfunction "DI_4-DIN") (pintype "input"))
    )
    (net (code "18") (name "Net-(D253-DO)") (class "Default")
      (node (ref "D253") (pin "2-DOUT") (pinfunction "DO_2-DOUT") (pintype "output"))
      (node (ref "D254") (pin "4-DIN") (pinfunction "DI_4-DIN") (pintype "input"))
    )
    (net (code "19") (name "Net-(D254-DO)") (class "Default")
      (node (ref "D254") (pin "2-DOUT") (pinfunction "DO_2-DOUT") (pintype "output"))
      (node (ref "D255") (pin "4-DIN") (pinfunction "DI_4-DIN") (pintype "input"))
    )
    (net (code "20") (name "Net-(D255-DO)") (class "Default")
      (node (ref "D255") (pin "2-DOUT") (pinfunction "DO_2-DOUT") (pintype "output"))
      (node (ref "D256") (pin "4-DIN") (pinfunction "DI_4-DIN") (pintype "input"))
    )
    (net (code "21") (name "Net-(D256-DO)") (class "Default")
      (node (ref "D256") (pin "2-DOUT") (pinfunction "DO_2-DOUT") (pintype "output"))
      (node (ref "D257") (pin "4-DIN") (pinfunction "DI_4-DIN") (pintype "input"))
    )
    (net (code "22") (name "Net-(D257-DO)") (class "Default")
      (node (ref "D257") (pin "2-DOUT") (pinfunction "DO_2-DOUT") (pintype "output"))
      (node (ref "D258") (pin "4-DIN") (pinfunction "DI_4-DIN") (pintype "input"))
    )
    (net (code "23") (name "Net-(D258-DO)") (class "Default")
      (node (ref "D258") (pin "2-DOUT") (pinfunction "DO_2-DOUT") (pintype "output"))
      (node (ref "D259") (pin "4-DIN") (pinfunction "DI_4-DIN") (pintype "input"))
    )
    (net (code "24") (name "Net-(D259-DO)") (class "Default")
      (node (ref "D259") (pin "2-DOUT") (pinfunction "DO_2-DOUT") (pintype "output"))
      (node (ref "D260") (pin "4-DIN") (pinfunction "DI_4-DIN") (pintype "input"))
    )
    (net (code "25") (name "Net-(D260-DO)") (class "Default")
      (node (ref "D260") (pin "2-DOUT") (pinfunction "DO_2-DOUT") (pintype "output"))
      (node (ref "D261") (pin "4-DIN") (pinfunction "DI_4-DIN") (pintype "input"))
    )
    (net (code "26") (name "Net-(D261-DO)") (class "Default")
      (node (ref "D261") (pin "2-DOUT") (pinfunction "DO_2-DOUT") (pintype "output"))
      (node (ref "D262") (pin "4-DIN") (pinfunction "DI_4-DIN") (pintype "input"))
    )
    (net (code "27") (name "Net-(D262-DO)") (class "Default")
      (node (ref "D262") (pin "2-DOUT") (pinfunction "DO_2-DOUT") (pintype "output"))
      (node (ref "D263") (pin "4-DIN") (pinfunction "DI_4-DIN") (pintype "input"))
    )
    (net (code "28") (name "Net-(D263-DO)") (class "Default")
      (node (ref "D263") (pin "2-DOUT") (pinfunction "DO_2-DOUT") (pintype "output"))
      (node (ref "D264") (pin "4-DIN") (pinfunction "DI_4-DIN") (pintype "input"))
    )
    (net (code "29") (name "Net-(D264-DO)") (class "Default")
      (node (ref "D264") (pin "2-DOUT") (pinfunction "DO_2-DOUT") (pintype "output"))
      (node (ref "R17") (pin "2") (pinfunction "2_2") (pintype "passive"))
    )
    (net (code "30") (name "Net-(D265-DI)") (class "Default")
      (node (ref "D265") (pin "4-DIN") (pinfunction "DI_4-DIN") (pintype "input"))
      (node (ref "R17") (pin "1") (pinfunction "1_1") (pintype "passive"))
    )
    (net (code "31") (name "Net-(D265-DO)") (class "Default")
      (node (ref "D265") (pin "2-DOUT") (pinfunction "DO_2-DOUT") (pintype "output"))
      (node (ref "D266") (pin "4-DIN") (pinfunction "DI_4-DIN") (pintype "input"))
    )
    (net (code "32") (name "Net-(D266-DO)") (class "Default")
      (node (ref "D266") (pin "2-DOUT") (pinfunction "DO_2-DOUT") (pintype "output"))
      (node (ref "D267") (pin "4-DIN") (pinfunction "DI_4-DIN") (pintype "input"))
    )
    (net (code "33") (name "Net-(D267-DO)") (class "Default")
      (node (ref "D267") (pin "2-DOUT") (pinfunction "DO_2-DOUT") (pintype "output"))
      (node (ref "D268") (pin "4-DIN") (pinfunction "DI_4-DIN") (pintype "input"))
    )
    (net (code "34") (name "Net-(D268-DO)") (class "Default")
      (node (ref "D268") (pin "2-DOUT") (pinfunction "DO_2-DOUT") (pintype "output"))
      (node (ref "D269") (pin "4-DIN") (pinfunction "DI_4-DIN") (pintype "input"))
    )
    (net (code "35") (name "Net-(D269-DO)") (class "Default")
      (node (ref "D269") (pin "2-DOUT") (pinfunction "DO_2-DOUT") (pintype "output"))
      (node (ref "D270") (pin "4-DIN") (pinfunction "DI_4-DIN") (pintype "input"))
    )
    (net (code "36") (name "Net-(D270-DO)") (class "Default")
      (node (ref "D270") (pin "2-DOUT") (pinfunction "DO_2-DOUT") (pintype "output"))
      (node (ref "D271") (pin "4-DIN") (pinfunction "DI_4-DIN") (pintype "input"))
    )
    (net (code "37") (name "Net-(D271-DO)") (class "Default")
      (node (ref "D271") (pin "2-DOUT") (pinfunction "DO_2-DOUT") (pintype "output"))
      (node (ref "D272") (pin "4-DIN") (pinfunction "DI_4-DIN") (pintype "input"))
    )
    (net (code "38") (name "Net-(D272-DO)") (class "Default")
      (node (ref "D272") (pin "2-DOUT") (pinfunction "DO_2-DOUT") (pintype "output"))
      (node (ref "D273") (pin "4-DIN") (pinfunction "DI_4-DIN") (pintype "input"))
    )
    (net (code "39") (name "Net-(D273-DO)") (class "Default")
      (node (ref "D273") (pin "2-DOUT") (pinfunction "DO_2-DOUT") (pintype "output"))
      (node (ref "D274") (pin "4-DIN") (pinfunction "DI_4-DIN") (pintype "input"))
    )
    (net (code "40") (name "Net-(D274-DO)") (class "Default")
      (node (ref "D274") (pin "2-DOUT") (pinfunction "DO_2-DOUT") (pintype "output"))
      (node (ref "D275") (pin "4-DIN") (pinfunction "DI_4-DIN") (pintype "input"))
    )
    (net (code "41") (name "Net-(D275-DO)") (class "Default")
      (node (ref "D275") (pin "2-DOUT") (pinfunction "DO_2-DOUT") (pintype "output"))
      (node (ref "D276") (pin "4-DIN") (pinfunction "DI_4-DIN") (pintype "input"))
    )
    (net (code "42") (name "Net-(D276-DO)") (class "Default")
      (node (ref "D276") (pin "2-DOUT") (pinfunction "DO_2-DOUT") (pintype "output"))
      (node (ref "D277") (pin "4-DIN") (pinfunction "DI_4-DIN") (pintype "input"))
    )
    (net (code "43") (name "Net-(D277-DO)") (class "Default")
      (node (ref "D277") (pin "2-DOUT") (pinfunction "DO_2-DOUT") (pintype "output"))
      (node (ref "D278") (pin "4-DIN") (pinfunction "DI_4-DIN") (pintype "input"))
    )
    (net (code "44") (name "Net-(D278-DO)") (class "Default")
      (node (ref "D278") (pin "2-DOUT") (pinfunction "DO_2-DOUT") (pintype "output"))
      (node (ref "D279") (pin "4-DIN") (pinfunction "DI_4-DIN") (pintype "input"))
    )
    (net (code "45") (name "Net-(D279-DO)") (class "Default")
      (node (ref "D279") (pin "2-DOUT") (pinfunction "DO_2-DOUT") (pintype "output"))
      (node (ref "D280") (pin "4-DIN") (pinfunction "DI_4-DIN") (pintype "input"))
    )
    (net (code "46") (name "Net-(D280-DO)") (class "Default")
      (node (ref "D280") (pin "2-DOUT") (pinfunction "DO_2-DOUT") (pintype "output"))
      (node (ref "D281") (pin "4-DIN") (pinfunction "DI_4-DIN") (pintype "input"))
    )
    (net (code "47") (name "Net-(D281-DO)") (class "Default")
      (node (ref "D281") (pin "2-DOUT") (pinfunction "DO_2-DOUT") (pintype "output"))
      (node (ref "D282") (pin "4-DIN") (pinfunction "DI_4-DIN") (pintype "input"))
    )
    (net (code "48") (name "Net-(D282-DO)") (class "Default")
      (node (ref "D282") (pin "2-DOUT") (pinfunction "DO_2-DOUT") (pintype "output"))
      (node (ref "D283") (pin "4-DIN") (pinfunction "DI_4-DIN") (pintype "input"))
    )
    (net (code "49") (name "Net-(D283-DO)") (class "Default")
      (node (ref "D283") (pin "2-DOUT") (pinfunction "DO_2-DOUT") (pintype "output"))
      (node (ref "D284") (pin "4-DIN") (pinfunction "DI_4-DIN") (pintype "input"))
    )
    (net (code "50") (name "Net-(D284-DO)") (class "Default")
      (node (ref "D284") (pin "2-DOUT") (pinfunction "DO_2-DOUT") (pintype "output"))
      (node (ref "D285") (pin "4-DIN") (pinfunction "DI_4-DIN") (pintype "input"))
    )
    (net (code "51") (name "Net-(D285-DO)") (class "Default")
      (node (ref "D285") (pin "2-DOUT") (pinfunction "DO_2-DOUT") (pintype "output"))
      (node (ref "D286") (pin "4-DIN") (pinfunction "DI_4-DIN") (pintype "input"))
    )
    (net (code "52") (name "Net-(D286-DO)") (class "Default")
      (node (ref "D286") (pin "2-DOUT") (pinfunction "DO_2-DOUT") (pintype "output"))
      (node (ref "D287") (pin "4-DIN") (pinfunction "DI_4-DIN") (pintype "input"))
    )
    (net (code "53") (name "Net-(D287-DO)") (class "Default")
      (node (ref "D287") (pin "2-DOUT") (pinfunction "DO_2-DOUT") (pintype "output"))
      (node (ref "D288") (pin "4-DIN") (pinfunction "DI_4-DIN") (pintype "input"))
    )
    (net (code "54") (name "unconnected-(D288-DO-Pad2-DOUT)") (class "Default")
      (node (ref "D288") (pin "2-DOUT") (pinfunction "DO_2-DOUT") (pintype "output+no_connect"))
    )
  )
)
